# QCopterMV_SD_Sch.net
KiCad netlist of a schematic drawn in Altium Designer
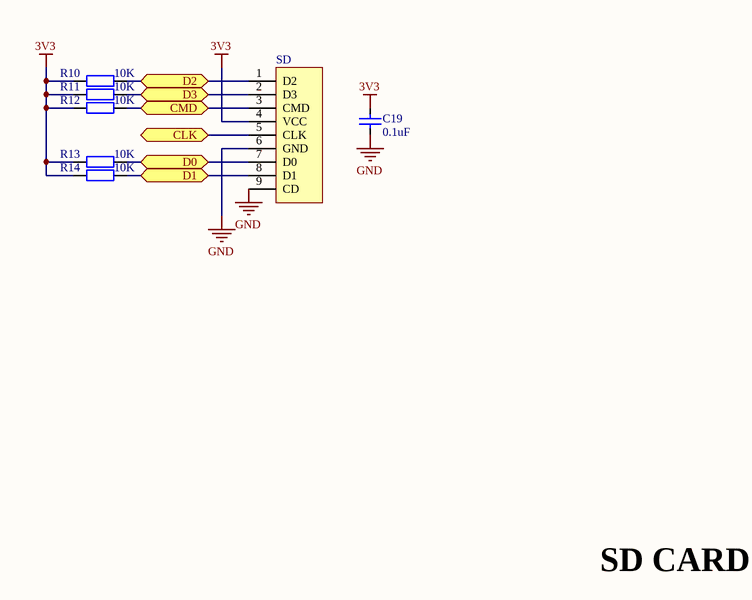
[diagram p0: QCopterMV_SD_Sch.SchDoc]

(export (version "E")
  (design (tool "Eeschema 10.0.6"))
  (components
    (comp (ref "C19")
      (value "0.1uF")
      (footprint "PCB_Passive:CAP_0603")
      (description "Capacitor")
      (fields (field (name "Comment") "Cap_0603"))
      (libsource (lib "SCH_Passive") (part "Cap_0603"))
    )
    (comp (ref "R10")
      (value "10K")
      (footprint "PCB_Passive:RES_0603")
      (description "Resistor")
      (fields (field (name "Comment") "Res_0603"))
      (libsource (lib "SCH_Passive") (part "Res_0603"))
    )
    (comp (ref "R11")
      (value "10K")
      (footprint "PCB_Passive:RES_0603")
      (description "Resistor")
      (fields (field (name "Comment") "Res_0603"))
      (libsource (lib "SCH_Passive") (part "Res_0603"))
    )
    (comp (ref "R12")
      (value "10K")
      (footprint "PCB_Passive:RES_0603")
      (description "Resistor")
      (fields (field (name "Comment") "Res_0603"))
      (libsource (lib "SCH_Passive") (part "Res_0603"))
    )
    (comp (ref "R13")
      (value "10K")
      (footprint "PCB_Passive:RES_0603")
      (description "Resistor")
      (fields (field (name "Comment") "Res_0603"))
      (libsource (lib "SCH_Passive") (part "Res_0603"))
    )
    (comp (ref "R14")
      (value "10K")
      (footprint "PCB_Passive:RES_0603")
      (description "Resistor")
      (fields (field (name "Comment") "Res_0603"))
      (libsource (lib "SCH_Passive") (part "Res_0603"))
    )
    (comp (ref "SD")
      (value "SD_Card_TF")
      (footprint "PCB_SDCard:SD_Card_TF")
      (description "SD")
      (libsource (lib "SCH_SDCard") (part "SD_Card_TF"))
    )
  )
  (nets
    (net (code "1") (name "/CLK") (class "Default")
      (node (ref "SD") (pin "5") (pinfunction "CLK_5") (pintype "passive"))
    )
    (net (code "2") (name "/CMD") (class "Default")
      (node (ref "R12") (pin "2") (pinfunction "2_2") (pintype "passive"))
      (node (ref "SD") (pin "3") (pinfunction "CMD_3") (pintype "passive"))
    )
    (net (code "3") (name "/D0") (class "Default")
      (node (ref "R13") (pin "2") (pinfunction "2_2") (pintype "passive"))
      (node (ref "SD") (pin "7") (pinfunction "D0_7") (pintype "passive"))
    )
    (net (code "4") (name "/D1") (class "Default")
      (node (ref "R14") (pin "2") (pinfunction "2_2") (pintype "passive"))
      (node (ref "SD") (pin "8") (pinfunction "D1_8") (pintype "passive"))
    )
    (net (code "5") (name "/D2") (class "Default")
      (node (ref "R10") (pin "2") (pinfunction "2_2") (pintype "passive"))
      (node (ref "SD") (pin "1") (pinfunction "D2_1") (pintype "passive"))
    )
    (net (code "6") (name "/D3") (class "Default")
      (node (ref "R11") (pin "2") (pinfunction "2_2") (pintype "passive"))
      (node (ref "SD") (pin "2") (pinfunction "D3_2") (pintype "passive"))
    )
    (net (code "8") (name "3V3") (class "Default")
      (node (ref "C19") (pin "2") (pinfunction "2_2") (pintype "passive"))
      (node (ref "R10") (pin "1") (pinfunction "1_1") (pintype "passive"))
      (node (ref "R11") (pin "1") (pinfunction "1_1") (pintype "passive"))
      (node (ref "R12") (pin "1") (pinfunction "1_1") (pintype "passive"))
      (node (ref "R13") (pin "1") (pinfunction "1_1") (pintype "passive"))
      (node (ref "R14") (pin "1") (pinfunction "1_1") (pintype "passive"))
      (node (ref "SD") (pin "4") (pinfunction "VCC_4") (pintype "passive"))
    )
    (net (code "9") (name "GND") (class "Default")
      (node (ref "C19") (pin "1") (pinfunction "1_1") (pintype "passive"))
      (node (ref "SD") (pin "6") (pinfunction "GND_6") (pintype "passive"))
      (node (ref "SD") (pin "9") (pinfunction "CD_9") (pintype "passive"))
    )
  )
)
